# attiny_project.net
KiCad netlist of a schematic drawn in EAGLE
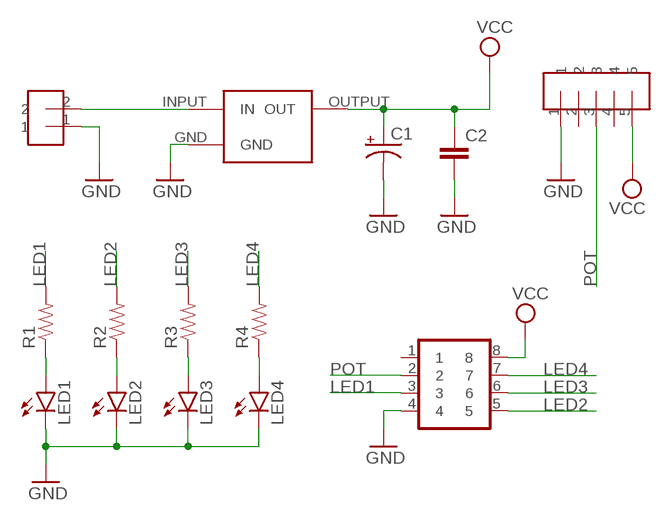
[diagram p0: schematic, sheet 1]

(export (version "E")
  (design (tool "Eeschema 10.0.6"))
  (components
    (comp (ref "C1")
      (value "CAP_POLPTH2")
      (footprint "eagle-import:CPOL-RADIAL-10UF-25V")
      (libsource (lib "eagle-import") (part "CAP_POLPTH2"))
    )
    (comp (ref "C2")
      (value "CAPPTH")
      (footprint "eagle-import:CAP-PTH-SMALL")
      (libsource (lib "eagle-import") (part "CAPPTH"))
    )
    (comp (ref "LED1")
      (value "LED5MM")
      (footprint "eagle-import:LED5MM")
      (libsource (lib "eagle-import") (part "LED5MM"))
    )
    (comp (ref "LED2")
      (value "LED5MM")
      (footprint "eagle-import:LED5MM")
      (libsource (lib "eagle-import") (part "LED5MM"))
    )
    (comp (ref "LED3")
      (value "LED5MM")
      (footprint "eagle-import:LED5MM")
      (libsource (lib "eagle-import") (part "LED5MM"))
    )
    (comp (ref "LED4")
      (value "LED5MM")
      (footprint "eagle-import:LED5MM")
      (libsource (lib "eagle-import") (part "LED5MM"))
    )
    (comp (ref "R1")
      (value "RESISTORPTH-1/4W")
      (footprint "eagle-import:AXIAL-0.4")
      (libsource (lib "eagle-import") (part "RESISTORPTH-1/4W"))
    )
    (comp (ref "R2")
      (value "RESISTORPTH-1/4W")
      (footprint "eagle-import:AXIAL-0.4")
      (libsource (lib "eagle-import") (part "RESISTORPTH-1/4W"))
    )
    (comp (ref "R3")
      (value "RESISTORPTH-1/4W")
      (footprint "eagle-import:AXIAL-0.4")
      (libsource (lib "eagle-import") (part "RESISTORPTH-1/4W"))
    )
    (comp (ref "R4")
      (value "RESISTORPTH-1/4W")
      (footprint "eagle-import:AXIAL-0.4")
      (libsource (lib "eagle-import") (part "RESISTORPTH-1/4W"))
    )
    (comp (ref "U$1")
      (value "SOCKET-8PINDIP")
      (footprint "eagle-import:SOCKET-8PIN")
      (libsource (lib "eagle-import") (part "SOCKET-8PINDIP"))
    )
    (comp (ref "U$2")
      (value "HEADER-5")
      (footprint "eagle-import:HEADER-5")
      (libsource (lib "eagle-import") (part "HEADER-5"))
    )
    (comp (ref "U$3")
      (value "REGULATOR5V-MC7805CT")
      (footprint "eagle-import:REGULATOR-7805")
      (libsource (lib "eagle-import") (part "REGULATOR5V-MC7805CT"))
    )
    (comp (ref "U$4")
      (value "HEADER-2")
      (footprint "eagle-import:HEADER-2")
      (libsource (lib "eagle-import") (part "HEADER-2"))
    )
  )
  (nets
    (net (code "1") (name "/LED1") (class "Default")
      (node (ref "R1") (pin "P$2") (pinfunction "2_P$2") (pintype "passive"))
      (node (ref "U$1") (pin "3") (pinfunction "3_3") (pintype "bidirectional"))
    )
    (net (code "2") (name "/LED2") (class "Default")
      (node (ref "R2") (pin "P$2") (pinfunction "2_P$2") (pintype "passive"))
      (node (ref "U$1") (pin "5") (pinfunction "5_5") (pintype "bidirectional"))
    )
    (net (code "3") (name "/LED3") (class "Default")
      (node (ref "R3") (pin "P$2") (pinfunction "2_P$2") (pintype "passive"))
      (node (ref "U$1") (pin "6") (pinfunction "6_6") (pintype "bidirectional"))
    )
    (net (code "4") (name "/LED4") (class "Default")
      (node (ref "R4") (pin "P$2") (pinfunction "2_P$2") (pintype "passive"))
      (node (ref "U$1") (pin "7") (pinfunction "7_7") (pintype "bidirectional"))
    )
    (net (code "5") (name "/POT") (class "Default")
      (node (ref "U$1") (pin "2") (pinfunction "2_2") (pintype "bidirectional"))
      (node (ref "U$2") (pin "3") (pinfunction "3_3") (pintype "bidirectional"))
    )
    (net (code "6") (name "GND") (class "Default")
      (node (ref "C1") (pin "2") (pinfunction "-_2") (pintype "passive"))
      (node (ref "C2") (pin "2") (pinfunction "2_2") (pintype "passive"))
      (node (ref "LED1") (pin "K") (pinfunction "C_K") (pintype "passive"))
      (node (ref "LED2") (pin "K") (pinfunction "C_K") (pintype "passive"))
      (node (ref "LED3") (pin "K") (pinfunction "C_K") (pintype "passive"))
      (node (ref "LED4") (pin "K") (pinfunction "C_K") (pintype "passive"))
      (node (ref "U$1") (pin "4") (pinfunction "4_4") (pintype "bidirectional"))
      (node (ref "U$2") (pin "1") (pinfunction "1_1") (pintype "bidirectional"))
      (node (ref "U$3") (pin "GND") (pinfunction "GND_GND") (pintype "bidirectional"))
      (node (ref "U$4") (pin "1") (pinfunction "1_1") (pintype "bidirectional"))
    )
    (net (code "7") (name "Net-(R1-1)") (class "Default")
      (node (ref "LED1") (pin "A") (pinfunction "A_A") (pintype "passive"))
      (node (ref "R1") (pin "P$1") (pinfunction "1_P$1") (pintype "passive"))
    )
    (net (code "8") (name "Net-(R2-1)") (class "Default")
      (node (ref "LED2") (pin "A") (pinfunction "A_A") (pintype "passive"))
      (node (ref "R2") (pin "P$1") (pinfunction "1_P$1") (pintype "passive"))
    )
    (net (code "9") (name "Net-(R3-1)") (class "Default")
      (node (ref "LED3") (pin "A") (pinfunction "A_A") (pintype "passive"))
      (node (ref "R3") (pin "P$1") (pinfunction "1_P$1") (pintype "passive"))
    )
    (net (code "10") (name "Net-(R4-1)") (class "Default")
      (node (ref "LED4") (pin "A") (pinfunction "A_A") (pintype "passive"))
      (node (ref "R4") (pin "P$1") (pinfunction "1_P$1") (pintype "passive"))
    )
    (net (code "11") (name "Net-(U$3-IN)") (class "Default")
      (node (ref "U$3") (pin "INPUT") (pinfunction "IN_INPUT") (pintype "bidirectional"))
      (node (ref "U$4") (pin "2") (pinfunction "2_2") (pintype "bidirectional"))
    )
    (net (code "12") (name "VCC") (class "Default")
      (node (ref "C1") (pin "1") (pinfunction "+_1") (pintype "passive"))
      (node (ref "C2") (pin "1") (pinfunction "1_1") (pintype "passive"))
      (node (ref "U$1") (pin "8") (pinfunction "8_8") (pintype "bidirectional"))
      (node (ref "U$2") (pin "5") (pinfunction "5_5") (pintype "bidirectional"))
      (node (ref "U$3") (pin "OUTPUT") (pinfunction "OUT_OUTPUT") (pintype "bidirectional"))
    )
    (net (code "13") (name "unconnected-(U$1-Pad1)") (class "Default")
      (node (ref "U$1") (pin "1") (pinfunction "1_1") (pintype "bidirectional"))
    )
    (net (code "14") (name "unconnected-(U$2-Pad2)") (class "Default")
      (node (ref "U$2") (pin "2") (pinfunction "2_2") (pintype "bidirectional"))
    )
    (net (code "15") (name "unconnected-(U$2-Pad4)") (class "Default")
      (node (ref "U$2") (pin "4") (pinfunction "4_4") (pintype "bidirectional"))
    )
  )
)
